# item_2022_BlockDiagram_02.net
KiCad netlist of a schematic drawn in EAGLE
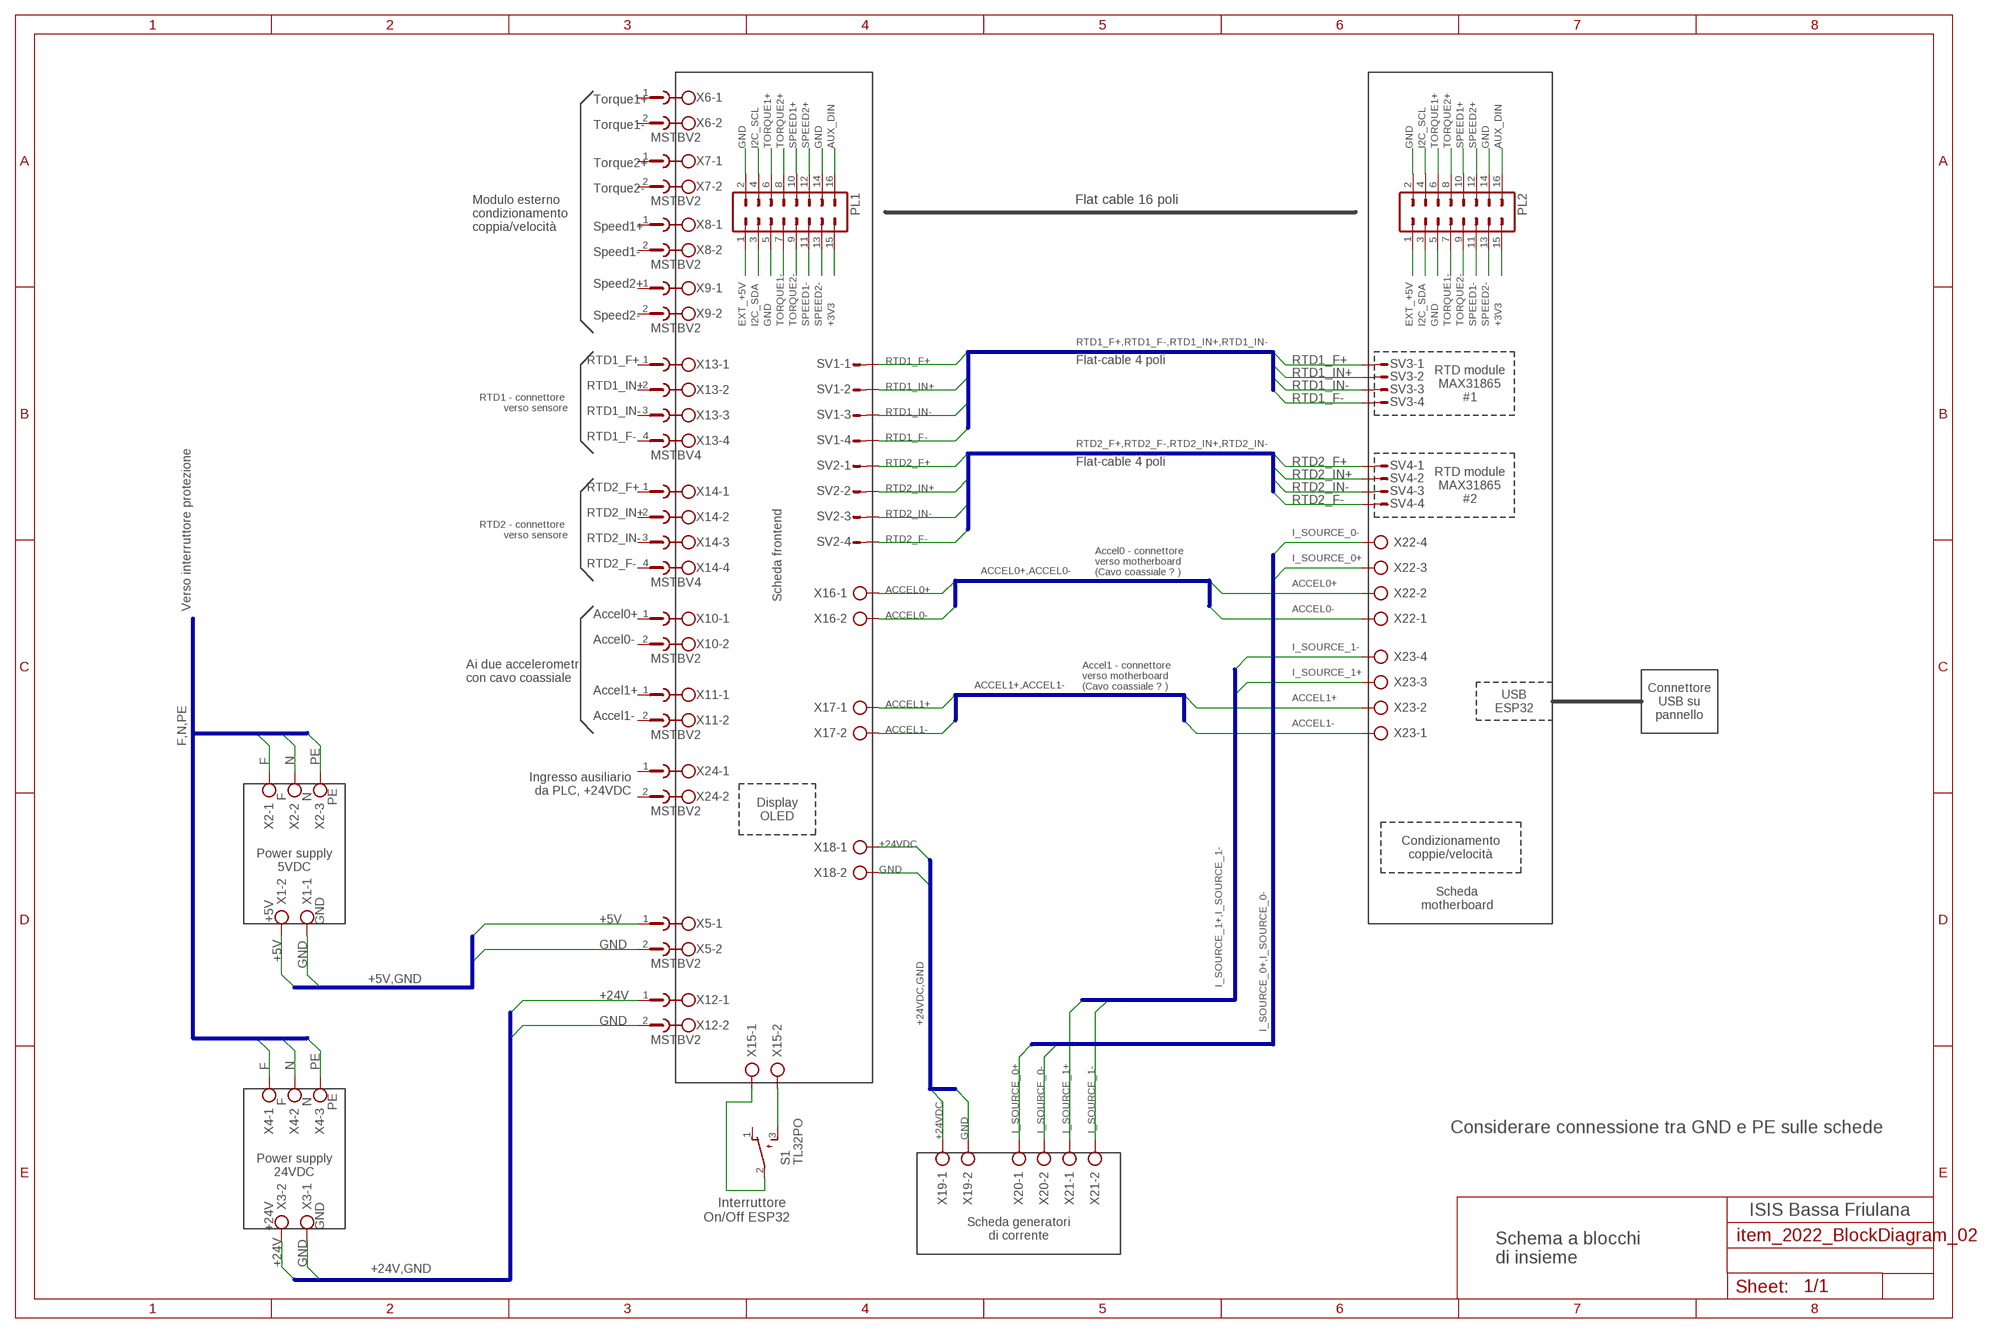
[diagram p0: schematic, sheet 1]

(export (version "E")
  (design (tool "Eeschema 10.0.6"))
  (components
    (comp (ref "PL1")
      (value "16V")
      (footprint "eagle-import:16V")
      (libsource (lib "eagle-import") (part "16V"))
    )
    (comp (ref "PL2")
      (value "16V")
      (footprint "eagle-import:16V")
      (libsource (lib "eagle-import") (part "16V"))
    )
    (comp (ref "S1")
      (value "TL32PO")
      (footprint "eagle-import:TL3XPO")
      (libsource (lib "eagle-import") (part "TL32PO"))
    )
    (comp (ref "SV1")
      (value "S04P")
      (footprint "eagle-import:S04P")
      (libsource (lib "eagle-import") (part "S04P"))
    )
    (comp (ref "SV2")
      (value "S04P")
      (footprint "eagle-import:S04P")
      (libsource (lib "eagle-import") (part "S04P"))
    )
    (comp (ref "SV3")
      (value "S04P")
      (footprint "eagle-import:S04P")
      (libsource (lib "eagle-import") (part "S04P"))
    )
    (comp (ref "SV4")
      (value "S04P")
      (footprint "eagle-import:S04P")
      (libsource (lib "eagle-import") (part "S04P"))
    )
    (comp (ref "X1")
      (value "+5V")
      (footprint "eagle-import:AK500_2")
      (libsource (lib "eagle-import") (part "AK500/2"))
    )
    (comp (ref "X2")
      (value "AK500/3")
      (footprint "eagle-import:AK500_3")
      (libsource (lib "eagle-import") (part "AK500/3"))
    )
    (comp (ref "X3")
      (value "+5V")
      (footprint "eagle-import:AK500_2")
      (libsource (lib "eagle-import") (part "AK500/2"))
    )
    (comp (ref "X4")
      (value "AK500/3")
      (footprint "eagle-import:AK500_3")
      (libsource (lib "eagle-import") (part "AK500/3"))
    )
    (comp (ref "X5")
      (value "MSTBV2")
      (footprint "eagle-import:MSTBV2")
      (fields (field (name "MPN") "MSTBV 2,5/2-GF-5.08"))
      (libsource (lib "eagle-import") (part "MSTBV2"))
    )
    (comp (ref "X6")
      (value "MSTBV2")
      (footprint "eagle-import:MSTBV2")
      (fields (field (name "MPN") "MSTBV 2,5/2-GF-5.08"))
      (libsource (lib "eagle-import") (part "MSTBV2"))
    )
    (comp (ref "X7")
      (value "MSTBV2")
      (footprint "eagle-import:MSTBV2")
      (fields (field (name "MPN") "MSTBV 2,5/2-GF-5.08"))
      (libsource (lib "eagle-import") (part "MSTBV2"))
    )
    (comp (ref "X8")
      (value "MSTBV2")
      (footprint "eagle-import:MSTBV2")
      (fields (field (name "MPN") "MSTBV 2,5/2-GF-5.08"))
      (libsource (lib "eagle-import") (part "MSTBV2"))
    )
    (comp (ref "X9")
      (value "MSTBV2")
      (footprint "eagle-import:MSTBV2")
      (fields (field (name "MPN") "MSTBV 2,5/2-GF-5.08"))
      (libsource (lib "eagle-import") (part "MSTBV2"))
    )
    (comp (ref "X10")
      (value "MSTBV2")
      (footprint "eagle-import:MSTBV2")
      (fields (field (name "MPN") "MSTBV 2,5/2-GF-5.08"))
      (libsource (lib "eagle-import") (part "MSTBV2"))
    )
    (comp (ref "X11")
      (value "MSTBV2")
      (footprint "eagle-import:MSTBV2")
      (fields (field (name "MPN") "MSTBV 2,5/2-GF-5.08"))
      (libsource (lib "eagle-import") (part "MSTBV2"))
    )
    (comp (ref "X12")
      (value "MSTBV2")
      (footprint "eagle-import:MSTBV2")
      (fields (field (name "MPN") "MSTBV 2,5/2-GF-5.08"))
      (libsource (lib "eagle-import") (part "MSTBV2"))
    )
    (comp (ref "X13")
      (value "MSTBV4")
      (footprint "eagle-import:MSTBV4")
      (fields (field (name "MPN") "MSTBV 2,5/4-GF-5.08"))
      (libsource (lib "eagle-import") (part "MSTBV4"))
    )
    (comp (ref "X14")
      (value "MSTBV4")
      (footprint "eagle-import:MSTBV4")
      (fields (field (name "MPN") "MSTBV 2,5/4-GF-5.08"))
      (libsource (lib "eagle-import") (part "MSTBV4"))
    )
    (comp (ref "X15")
      (value "AK500/2")
      (footprint "eagle-import:AK500_2")
      (libsource (lib "eagle-import") (part "AK500/2"))
    )
    (comp (ref "X16")
      (value "AK500/2")
      (footprint "eagle-import:AK500_2")
      (libsource (lib "eagle-import") (part "AK500/2"))
    )
    (comp (ref "X17")
      (value "AK500/2")
      (footprint "eagle-import:AK500_2")
      (libsource (lib "eagle-import") (part "AK500/2"))
    )
    (comp (ref "X18")
      (value "AK500/2")
      (footprint "eagle-import:AK500_2")
      (libsource (lib "eagle-import") (part "AK500/2"))
    )
    (comp (ref "X19")
      (value "AK500/2")
      (footprint "eagle-import:AK500_2")
      (libsource (lib "eagle-import") (part "AK500/2"))
    )
    (comp (ref "X20")
      (value "AK500/2")
      (footprint "eagle-import:AK500_2")
      (libsource (lib "eagle-import") (part "AK500/2"))
    )
    (comp (ref "X21")
      (value "AK500/2")
      (footprint "eagle-import:AK500_2")
      (libsource (lib "eagle-import") (part "AK500/2"))
    )
    (comp (ref "X22")
      (value "AK500/4")
      (footprint "eagle-import:AK500_4")
      (libsource (lib "eagle-import") (part "AK500/4"))
    )
    (comp (ref "X23")
      (value "AK500/4")
      (footprint "eagle-import:AK500_4")
      (libsource (lib "eagle-import") (part "AK500/4"))
    )
    (comp (ref "X24")
      (value "MSTBV2")
      (footprint "eagle-import:MSTBV2")
      (fields (field (name "MPN") "MSTBV 2,5/2-GF-5.08"))
      (libsource (lib "eagle-import") (part "MSTBV2"))
    )
  )
  (nets
    (net (code "1") (name "/+3V3") (class "Default")
      (node (ref "PL1") (pin "15") (pinfunction "15_15") (pintype "passive"))
      (node (ref "PL2") (pin "15") (pinfunction "15_15") (pintype "passive"))
    )
    (net (code "2") (name "/+5V") (class "Default")
      (node (ref "X1") (pin "2") (pinfunction "KL_2") (pintype "passive"))
      (node (ref "X5") (pin "1") (pinfunction "1_1") (pintype "passive"))
    )
    (net (code "3") (name "/+24V") (class "Default")
      (node (ref "X12") (pin "1") (pinfunction "1_1") (pintype "passive"))
      (node (ref "X3") (pin "2") (pinfunction "KL_2") (pintype "passive"))
    )
    (net (code "4") (name "/+24VDC") (class "Default")
      (node (ref "X18") (pin "1") (pinfunction "KL_1") (pintype "passive"))
      (node (ref "X19") (pin "1") (pinfunction "KL_1") (pintype "passive"))
    )
    (net (code "5") (name "/ACCEL0+") (class "Default")
      (node (ref "X16") (pin "1") (pinfunction "KL_1") (pintype "passive"))
      (node (ref "X22") (pin "2") (pinfunction "KL_2") (pintype "passive"))
    )
    (net (code "6") (name "/ACCEL0-") (class "Default")
      (node (ref "X16") (pin "2") (pinfunction "KL_2") (pintype "passive"))
      (node (ref "X22") (pin "1") (pinfunction "KL_1") (pintype "passive"))
    )
    (net (code "7") (name "/ACCEL1+") (class "Default")
      (node (ref "X17") (pin "1") (pinfunction "KL_1") (pintype "passive"))
      (node (ref "X23") (pin "2") (pinfunction "KL_2") (pintype "passive"))
    )
    (net (code "8") (name "/ACCEL1-") (class "Default")
      (node (ref "X17") (pin "2") (pinfunction "KL_2") (pintype "passive"))
      (node (ref "X23") (pin "1") (pinfunction "KL_1") (pintype "passive"))
    )
    (net (code "9") (name "/AUX_DIN") (class "Default")
      (node (ref "PL1") (pin "16") (pinfunction "16_16") (pintype "passive"))
      (node (ref "PL2") (pin "16") (pinfunction "16_16") (pintype "passive"))
    )
    (net (code "10") (name "/EXT_+5V") (class "Default")
      (node (ref "PL1") (pin "1") (pinfunction "1_1") (pintype "passive"))
      (node (ref "PL2") (pin "1") (pinfunction "1_1") (pintype "passive"))
    )
    (net (code "11") (name "/F") (class "Default")
      (node (ref "X2") (pin "1") (pinfunction "KL_1") (pintype "passive"))
      (node (ref "X4") (pin "1") (pinfunction "KL_1") (pintype "passive"))
    )
    (net (code "12") (name "/GND") (class "Default")
      (node (ref "PL1") (pin "14") (pinfunction "14_14") (pintype "passive"))
      (node (ref "PL1") (pin "2") (pinfunction "2_2") (pintype "passive"))
      (node (ref "PL1") (pin "5") (pinfunction "5_5") (pintype "passive"))
      (node (ref "PL2") (pin "14") (pinfunction "14_14") (pintype "passive"))
      (node (ref "PL2") (pin "2") (pinfunction "2_2") (pintype "passive"))
      (node (ref "PL2") (pin "5") (pinfunction "5_5") (pintype "passive"))
      (node (ref "X1") (pin "1") (pinfunction "KL_1") (pintype "passive"))
      (node (ref "X12") (pin "2") (pinfunction "1_2") (pintype "passive"))
      (node (ref "X18") (pin "2") (pinfunction "KL_2") (pintype "passive"))
      (node (ref "X19") (pin "2") (pinfunction "KL_2") (pintype "passive"))
      (node (ref "X3") (pin "1") (pinfunction "KL_1") (pintype "passive"))
      (node (ref "X5") (pin "2") (pinfunction "1_2") (pintype "passive"))
    )
    (net (code "13") (name "/I2C_SCL") (class "Default")
      (node (ref "PL1") (pin "4") (pinfunction "4_4") (pintype "passive"))
      (node (ref "PL2") (pin "4") (pinfunction "4_4") (pintype "passive"))
    )
    (net (code "14") (name "/I2C_SDA") (class "Default")
      (node (ref "PL1") (pin "3") (pinfunction "3_3") (pintype "passive"))
      (node (ref "PL2") (pin "3") (pinfunction "3_3") (pintype "passive"))
    )
    (net (code "15") (name "/I_SOURCE_0+") (class "Default")
      (node (ref "X20") (pin "1") (pinfunction "KL_1") (pintype "passive"))
      (node (ref "X22") (pin "3") (pinfunction "KL_3") (pintype "passive"))
    )
    (net (code "16") (name "/I_SOURCE_0-") (class "Default")
      (node (ref "X20") (pin "2") (pinfunction "KL_2") (pintype "passive"))
      (node (ref "X22") (pin "4") (pinfunction "KL_4") (pintype "passive"))
    )
    (net (code "17") (name "/I_SOURCE_1+") (class "Default")
      (node (ref "X21") (pin "1") (pinfunction "KL_1") (pintype "passive"))
      (node (ref "X23") (pin "3") (pinfunction "KL_3") (pintype "passive"))
    )
    (net (code "18") (name "/I_SOURCE_1-") (class "Default")
      (node (ref "X21") (pin "2") (pinfunction "KL_2") (pintype "passive"))
      (node (ref "X23") (pin "4") (pinfunction "KL_4") (pintype "passive"))
    )
    (net (code "19") (name "/N") (class "Default")
      (node (ref "X2") (pin "2") (pinfunction "KL_2") (pintype "passive"))
      (node (ref "X4") (pin "2") (pinfunction "KL_2") (pintype "passive"))
    )
    (net (code "20") (name "/PE") (class "Default")
      (node (ref "X2") (pin "3") (pinfunction "KL_3") (pintype "passive"))
      (node (ref "X4") (pin "3") (pinfunction "KL_3") (pintype "passive"))
    )
    (net (code "21") (name "/RTD1_F+") (class "Default")
      (node (ref "SV1") (pin "1") (pinfunction "S_1") (pintype "passive"))
      (node (ref "SV3") (pin "1") (pinfunction "S_1") (pintype "passive"))
    )
    (net (code "22") (name "/RTD1_F-") (class "Default")
      (node (ref "SV1") (pin "4") (pinfunction "S_4") (pintype "passive"))
      (node (ref "SV3") (pin "4") (pinfunction "S_4") (pintype "passive"))
    )
    (net (code "23") (name "/RTD1_IN+") (class "Default")
      (node (ref "SV1") (pin "2") (pinfunction "S_2") (pintype "passive"))
      (node (ref "SV3") (pin "2") (pinfunction "S_2") (pintype "passive"))
    )
    (net (code "24") (name "/RTD1_IN-") (class "Default")
      (node (ref "SV1") (pin "3") (pinfunction "S_3") (pintype "passive"))
      (node (ref "SV3") (pin "3") (pinfunction "S_3") (pintype "passive"))
    )
    (net (code "25") (name "/RTD2_F+") (class "Default")
      (node (ref "SV2") (pin "1") (pinfunction "S_1") (pintype "passive"))
      (node (ref "SV4") (pin "1") (pinfunction "S_1") (pintype "passive"))
    )
    (net (code "26") (name "/RTD2_F-") (class "Default")
      (node (ref "SV2") (pin "4") (pinfunction "S_4") (pintype "passive"))
      (node (ref "SV4") (pin "4") (pinfunction "S_4") (pintype "passive"))
    )
    (net (code "27") (name "/RTD2_IN+") (class "Default")
      (node (ref "SV2") (pin "2") (pinfunction "S_2") (pintype "passive"))
      (node (ref "SV4") (pin "2") (pinfunction "S_2") (pintype "passive"))
    )
    (net (code "28") (name "/RTD2_IN-") (class "Default")
      (node (ref "SV2") (pin "3") (pinfunction "S_3") (pintype "passive"))
      (node (ref "SV4") (pin "3") (pinfunction "S_3") (pintype "passive"))
    )
    (net (code "29") (name "/SPEED1+") (class "Default")
      (node (ref "PL1") (pin "10") (pinfunction "10_10") (pintype "passive"))
      (node (ref "PL2") (pin "10") (pinfunction "10_10") (pintype "passive"))
    )
    (net (code "30") (name "/SPEED1-") (class "Default")
      (node (ref "PL1") (pin "11") (pinfunction "11_11") (pintype "passive"))
      (node (ref "PL2") (pin "11") (pinfunction "11_11") (pintype "passive"))
    )
    (net (code "31") (name "/SPEED2+") (class "Default")
      (node (ref "PL1") (pin "12") (pinfunction "12_12") (pintype "passive"))
      (node (ref "PL2") (pin "12") (pinfunction "12_12") (pintype "passive"))
    )
    (net (code "32") (name "/SPEED2-") (class "Default")
      (node (ref "PL1") (pin "13") (pinfunction "13_13") (pintype "passive"))
      (node (ref "PL2") (pin "13") (pinfunction "13_13") (pintype "passive"))
    )
    (net (code "33") (name "/TORQUE1+") (class "Default")
      (node (ref "PL1") (pin "6") (pinfunction "6_6") (pintype "passive"))
      (node (ref "PL2") (pin "6") (pinfunction "6_6") (pintype "passive"))
    )
    (net (code "34") (name "/TORQUE1-") (class "Default")
      (node (ref "PL1") (pin "7") (pinfunction "7_7") (pintype "passive"))
      (node (ref "PL2") (pin "7") (pinfunction "7_7") (pintype "passive"))
    )
    (net (code "35") (name "/TORQUE2+") (class "Default")
      (node (ref "PL1") (pin "8") (pinfunction "8_8") (pintype "passive"))
      (node (ref "PL2") (pin "8") (pinfunction "8_8") (pintype "passive"))
    )
    (net (code "36") (name "/TORQUE2-") (class "Default")
      (node (ref "PL1") (pin "9") (pinfunction "9_9") (pintype "passive"))
      (node (ref "PL2") (pin "9") (pinfunction "9_9") (pintype "passive"))
    )
    (net (code "47") (name "Net-(S1-P)") (class "Default")
      (node (ref "S1") (pin "2") (pinfunction "P_2") (pintype "passive"))
      (node (ref "X15") (pin "1") (pinfunction "KL_1") (pintype "passive"))
    )
    (net (code "48") (name "Net-(S1-S)") (class "Default")
      (node (ref "S1") (pin "3") (pinfunction "S_3") (pintype "passive"))
      (node (ref "X15") (pin "2") (pinfunction "KL_2") (pintype "passive"))
    )
    (net (code "49") (name "unconnected-(S1-O-Pad1)") (class "Default")
      (node (ref "S1") (pin "1") (pinfunction "O_1") (pintype "passive"))
    )
    (net (code "50") (name "unconnected-(X6-Pad1)") (class "Default")
      (node (ref "X6") (pin "1") (pinfunction "1_1") (pintype "passive"))
    )
    (net (code "51") (name "unconnected-(X6B-1-Pad2)") (class "Default")
      (node (ref "X6") (pin "2") (pinfunction "1_2") (pintype "passive"))
    )
    (net (code "52") (name "unconnected-(X7-Pad1)") (class "Default")
      (node (ref "X7") (pin "1") (pinfunction "1_1") (pintype "passive"))
    )
    (net (code "53") (name "unconnected-(X7B-1-Pad2)") (class "Default")
      (node (ref "X7") (pin "2") (pinfunction "1_2") (pintype "passive"))
    )
    (net (code "54") (name "unconnected-(X8-Pad1)") (class "Default")
      (node (ref "X8") (pin "1") (pinfunction "1_1") (pintype "passive"))
    )
    (net (code "55") (name "unconnected-(X8B-1-Pad2)") (class "Default")
      (node (ref "X8") (pin "2") (pinfunction "1_2") (pintype "passive"))
    )
    (net (code "56") (name "unconnected-(X9-Pad1)") (class "Default")
      (node (ref "X9") (pin "1") (pinfunction "1_1") (pintype "passive"))
    )
    (net (code "57") (name "unconnected-(X9B-1-Pad2)") (class "Default")
      (node (ref "X9") (pin "2") (pinfunction "1_2") (pintype "passive"))
    )
    (net (code "58") (name "unconnected-(X10-Pad1)") (class "Default")
      (node (ref "X10") (pin "1") (pinfunction "1_1") (pintype "passive"))
    )
    (net (code "59") (name "unconnected-(X10B-1-Pad2)") (class "Default")
      (node (ref "X10") (pin "2") (pinfunction "1_2") (pintype "passive"))
    )
    (net (code "60") (name "unconnected-(X11-Pad1)") (class "Default")
      (node (ref "X11") (pin "1") (pinfunction "1_1") (pintype "passive"))
    )
    (net (code "61") (name "unconnected-(X11B-1-Pad2)") (class "Default")
      (node (ref "X11") (pin "2") (pinfunction "1_2") (pintype "passive"))
    )
    (net (code "62") (name "unconnected-(X13-Pad1)") (class "Default")
      (node (ref "X13") (pin "1") (pinfunction "1_1") (pintype "passive"))
    )
    (net (code "63") (name "unconnected-(X13B-1-Pad2)") (class "Default")
      (node (ref "X13") (pin "2") (pinfunction "1_2") (pintype "passive"))
    )
    (net (code "64") (name "unconnected-(X13C-1-Pad3)") (class "Default")
      (node (ref "X13") (pin "3") (pinfunction "1_3") (pintype "passive"))
    )
    (net (code "65") (name "unconnected-(X13D-1-Pad4)") (class "Default")
      (node (ref "X13") (pin "4") (pinfunction "1_4") (pintype "passive"))
    )
    (net (code "66") (name "unconnected-(X14-Pad1)") (class "Default")
      (node (ref "X14") (pin "1") (pinfunction "1_1") (pintype "passive"))
    )
    (net (code "67") (name "unconnected-(X14B-1-Pad2)") (class "Default")
      (node (ref "X14") (pin "2") (pinfunction "1_2") (pintype "passive"))
    )
    (net (code "68") (name "unconnected-(X14C-1-Pad3)") (class "Default")
      (node (ref "X14") (pin "3") (pinfunction "1_3") (pintype "passive"))
    )
    (net (code "69") (name "unconnected-(X14D-1-Pad4)") (class "Default")
      (node (ref "X14") (pin "4") (pinfunction "1_4") (pintype "passive"))
    )
    (net (code "70") (name "unconnected-(X24-Pad1)") (class "Default")
      (node (ref "X24") (pin "1") (pinfunction "1_1") (pintype "passive"))
    )
    (net (code "71") (name "unconnected-(X24B-1-Pad2)") (class "Default")
      (node (ref "X24") (pin "2") (pinfunction "1_2") (pintype "passive"))
    )
  )
)
